# ZLS-028.net
KiCad netlist of a schematic drawn in Altium Designer
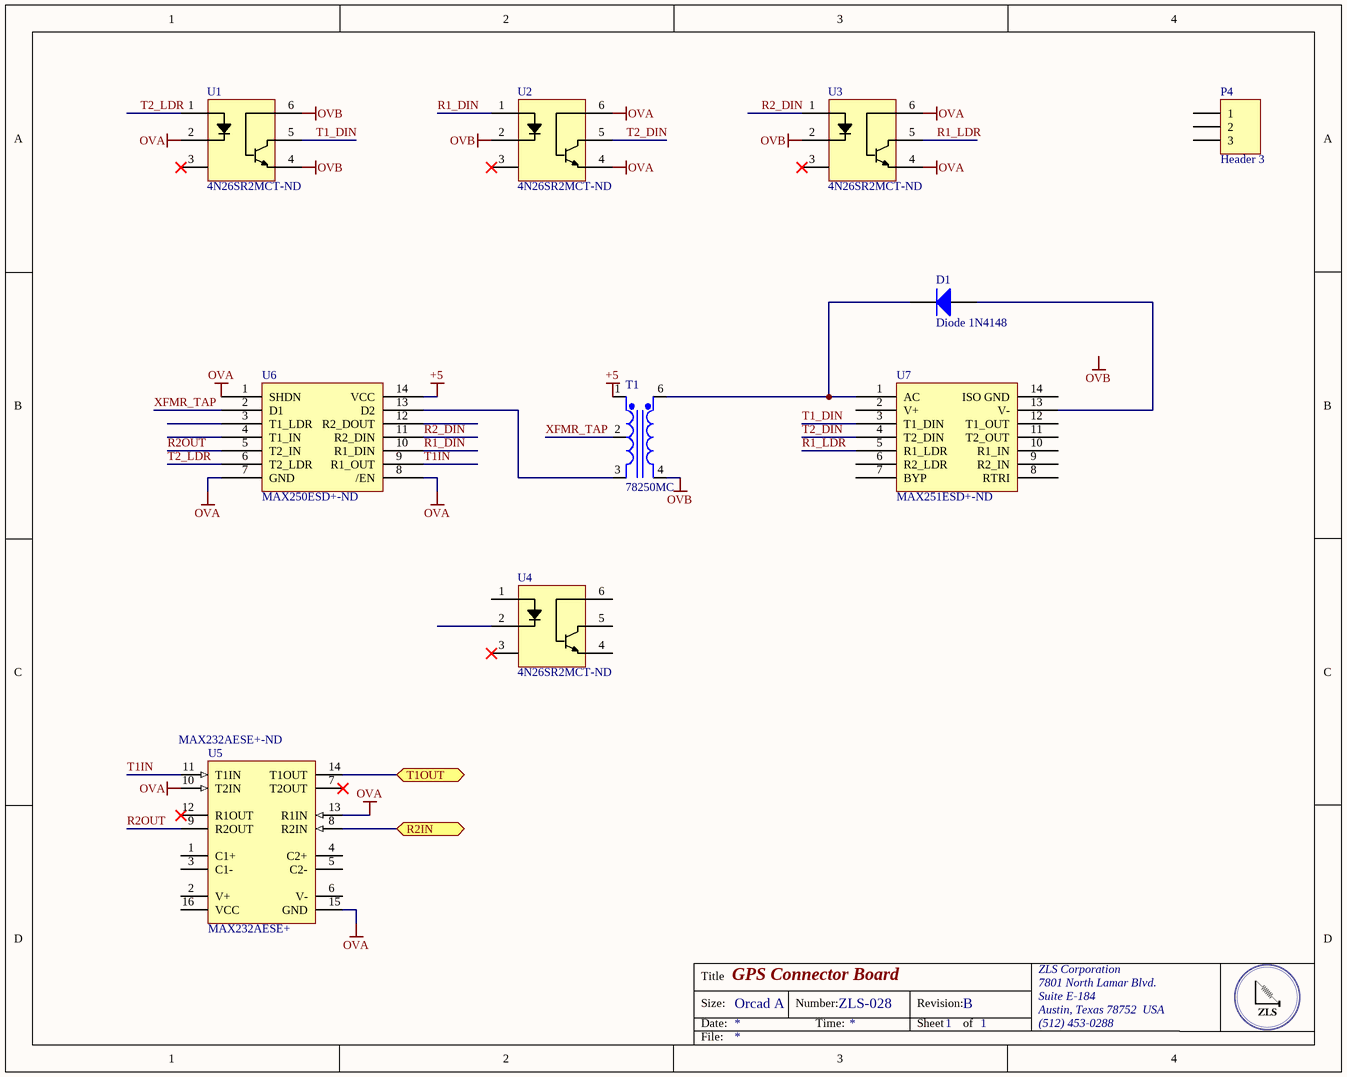
[diagram p0: ZLS-028.SchDoc]

(export (version "E")
  (design (tool "Eeschema 10.0.6"))
  (components
    (comp (ref "D1")
      (value "Diode 1N4148")
      (footprint "DO-35")
      (description "High Conductance Fast Diode")
      (fields (field (name "PUBLISHER") "Altium Limited"))
      (libsource (lib "Miscellaneous Devices") (part "Diode 1N4148"))
    )
    (comp (ref "P4")
      (value "Header 3")
      (footprint "HDR1X3")
      (description "Header, 3-Pin")
      (fields (field (name "PUBLISHER") "Altium Limited"))
      (libsource (lib "Miscellaneous Connectors") (part "Header 3"))
    )
    (comp (ref "T1")
      (value "78250MC")
      (footprint "78250MC")
      (description "Center-Tapped Transformer")
      (fields (field (name "MANUFACTURER") "Murata Power Solutions Inc."))
      (libsource (lib "Miscellaneous Devices") (part "Trans CT"))
    )
    (comp (ref "U1")
      (value "4N26")
      (footprint "6-SMD Gull Wing")
      (description "OPTOISO 4.17KV TRANS W/BASE 6SMD")
      (fields
        (field (name "SUPPLIER PART NUMBER 1") "4N26SR2MCT-ND")
        (field (name "MANUFACTURER") "ON Semiconductor")
        (field (name "MANUFACTURER PART NUMBER") "4N26SR2M")
      )
      (libsource (lib "ZLS_Schematic_lib") (part "4N26"))
    )
    (comp (ref "U2")
      (value "4N26")
      (footprint "6-SMD Gull Wing")
      (description "OPTOISO 4.17KV TRANS W/BASE 6SMD")
      (fields
        (field (name "SUPPLIER PART NUMBER 1") "4N26SR2MCT-ND")
        (field (name "MANUFACTURER") "ON Semiconductor")
        (field (name "MANUFACTURER PART NUMBER") "4N26SR2M")
      )
      (libsource (lib "ZLS_Schematic_lib") (part "4N26"))
    )
    (comp (ref "U3")
      (value "4N26")
      (footprint "6-SMD Gull Wing")
      (description "OPTOISO 4.17KV TRANS W/BASE 6SMD")
      (fields
        (field (name "SUPPLIER PART NUMBER 1") "4N26SR2MCT-ND")
        (field (name "MANUFACTURER") "ON Semiconductor")
        (field (name "MANUFACTURER PART NUMBER") "4N26SR2M")
      )
      (libsource (lib "ZLS_Schematic_lib") (part "4N26"))
    )
    (comp (ref "U4")
      (value "4N26")
      (footprint "6-SMD Gull Wing")
      (description "OPTOISO 4.17KV TRANS W/BASE 6SMD")
      (fields
        (field (name "SUPPLIER PART NUMBER 1") "4N26SR2MCT-ND")
        (field (name "MANUFACTURER") "ON Semiconductor")
        (field (name "MANUFACTURER PART NUMBER") "4N26SR2M")
      )
      (libsource (lib "ZLS_Schematic_lib") (part "4N26"))
    )
    (comp (ref "U5")
      (value "MAX232AESE+")
      (footprint "MAXM-S16+5_L")
      (description "IC TXRX 2/2 FULL RS232 16SOIC")
      (fields
        (field (name "SUPPLIER PART NUMBER 1") "MAX232AESE+-ND")
        (field (name "MANUFACTURER") "Maxim Integrated")
      )
      (libsource (lib "Altium Content Vault") (part "CMP-1675-00002-1"))
    )
    (comp (ref "U6")
      (value "MAX250ESD+")
      (footprint "MAX250ESD+")
      (fields (field (name "SUPPLIER PART NUMBER 1") "MAX250ESD+-ND"))
      (libsource (lib "ZLS_Schematic_lib") (part "MAX250ESD+"))
    )
    (comp (ref "U7")
      (value "MAX251ESD+")
      (footprint "MAX250ESD+")
      (fields
        (field (name "SUPPLIER PART NUMBER 1") "MAX251ESD+-ND")
        (field (name "MANUFACTURER") "Maxim Integrated")
      )
      (libsource (lib "ZLS_Schematic_lib") (part "MAX251ESD+"))
    )
  )
  (nets
    (net (code "1") (name "+5") (class "Default")
      (node (ref "T1") (pin "1") (pinfunction "Sec+_1") (pintype "passive"))
      (node (ref "U6") (pin "14") (pinfunction "VCC_14") (pintype "passive"))
    )
    (net (code "2") (name "/R1_DIN") (class "Default")
      (node (ref "U2") (pin "1") (pinfunction "1_1") (pintype "passive"))
      (node (ref "U6") (pin "10") (pinfunction "R1_DIN_10") (pintype "passive"))
    )
    (net (code "3") (name "/R1_LDR") (class "Default")
      (node (ref "U3") (pin "5") (pinfunction "5_5") (pintype "passive"))
      (node (ref "U7") (pin "5") (pinfunction "R1_LDR_5") (pintype "passive"))
    )
    (net (code "4") (name "/R2IN") (class "Default")
      (node (ref "U5") (pin "8") (pinfunction "R2IN_8") (pintype "input"))
    )
    (net (code "5") (name "/R2OUT") (class "Default")
      (node (ref "U5") (pin "9") (pinfunction "R2OUT_9") (pintype "tri_state"))
      (node (ref "U6") (pin "5") (pinfunction "T2_IN_5") (pintype "passive"))
    )
    (net (code "6") (name "/R2_DIN") (class "Default")
      (node (ref "U3") (pin "1") (pinfunction "1_1") (pintype "passive"))
      (node (ref "U6") (pin "11") (pinfunction "R2_DIN_11") (pintype "passive"))
    )
    (net (code "7") (name "/T1IN") (class "Default")
      (node (ref "U5") (pin "11") (pinfunction "T1IN_11") (pintype "input"))
      (node (ref "U6") (pin "9") (pinfunction "R1_OUT_9") (pintype "passive"))
    )
    (net (code "8") (name "/T1OUT") (class "Default")
      (node (ref "U5") (pin "14") (pinfunction "T1OUT_14") (pintype "tri_state"))
    )
    (net (code "9") (name "/T1_DIN") (class "Default")
      (node (ref "U1") (pin "5") (pinfunction "5_5") (pintype "passive"))
      (node (ref "U7") (pin "3") (pinfunction "T1_DIN_3") (pintype "passive"))
    )
    (net (code "10") (name "/T2_DIN") (class "Default")
      (node (ref "U2") (pin "5") (pinfunction "5_5") (pintype "passive"))
      (node (ref "U7") (pin "4") (pinfunction "T2_DIN_4") (pintype "passive"))
    )
    (net (code "11") (name "/T2_LDR") (class "Default")
      (node (ref "U1") (pin "1") (pinfunction "1_1") (pintype "passive"))
      (node (ref "U6") (pin "6") (pinfunction "T2_LDR_6") (pintype "passive"))
    )
    (net (code "12") (name "/XFMR_TAP") (class "Default")
      (node (ref "T1") (pin "2") (pinfunction "PriCT_2") (pintype "passive"))
      (node (ref "U6") (pin "2") (pinfunction "D1_2") (pintype "passive"))
    )
    (net (code "13") (name "Net-(D1-A)") (class "Default")
      (node (ref "D1") (pin "1") (pinfunction "A_1") (pintype "passive"))
      (node (ref "U7") (pin "13") (pinfunction "V-_13") (pintype "passive"))
    )
    (net (code "14") (name "Net-(D1-K)") (class "Default")
      (node (ref "D1") (pin "2") (pinfunction "K_2") (pintype "passive"))
      (node (ref "T1") (pin "6") (pinfunction "Pri+_6") (pintype "passive"))
      (node (ref "U7") (pin "1") (pinfunction "AC_1") (pintype "passive"))
    )
    (net (code "15") (name "Net-(T1-Sec-)") (class "Default")
      (node (ref "T1") (pin "3") (pinfunction "Sec-_3") (pintype "passive"))
      (node (ref "U6") (pin "13") (pinfunction "D2_13") (pintype "passive"))
    )
    (net (code "16") (name "OVA") (class "Default")
      (node (ref "U1") (pin "2") (pinfunction "2_2") (pintype "passive"))
      (node (ref "U2") (pin "4") (pinfunction "4_4") (pintype "passive"))
      (node (ref "U2") (pin "6") (pinfunction "6_6") (pintype "passive"))
      (node (ref "U3") (pin "4") (pinfunction "4_4") (pintype "passive"))
      (node (ref "U3") (pin "6") (pinfunction "6_6") (pintype "passive"))
      (node (ref "U5") (pin "10") (pinfunction "T2IN_10") (pintype "input"))
      (node (ref "U5") (pin "13") (pinfunction "R1IN_13") (pintype "input"))
      (node (ref "U5") (pin "15") (pinfunction "GND_15") (pintype "power_in"))
      (node (ref "U6") (pin "1") (pinfunction "SHDN_1") (pintype "passive"))
      (node (ref "U6") (pin "7") (pinfunction "GND_7") (pintype "passive"))
      (node (ref "U6") (pin "8") (pinfunction "/EN_8") (pintype "passive"))
    )
    (net (code "17") (name "OVB") (class "Default")
      (node (ref "T1") (pin "4") (pinfunction "Pri-_4") (pintype "passive"))
      (node (ref "U1") (pin "4") (pinfunction "4_4") (pintype "passive"))
      (node (ref "U1") (pin "6") (pinfunction "6_6") (pintype "passive"))
      (node (ref "U2") (pin "2") (pinfunction "2_2") (pintype "passive"))
      (node (ref "U3") (pin "2") (pinfunction "2_2") (pintype "passive"))
    )
    (net (code "18") (name "unconnected-(P4-Pad1)") (class "Default")
      (node (ref "P4") (pin "1") (pinfunction "1_1") (pintype "passive"))
    )
    (net (code "19") (name "unconnected-(P4-Pad2)") (class "Default")
      (node (ref "P4") (pin "2") (pinfunction "2_2") (pintype "passive"))
    )
    (net (code "20") (name "unconnected-(P4-Pad3)") (class "Default")
      (node (ref "P4") (pin "3") (pinfunction "3_3") (pintype "passive"))
    )
    (net (code "21") (name "unconnected-(U1-Pad3)") (class "Default")
      (node (ref "U1") (pin "3") (pinfunction "3_3") (pintype "passive+no_connect"))
    )
    (net (code "22") (name "unconnected-(U2-Pad3)") (class "Default")
      (node (ref "U2") (pin "3") (pinfunction "3_3") (pintype "passive+no_connect"))
    )
    (net (code "23") (name "unconnected-(U3-Pad3)") (class "Default")
      (node (ref "U3") (pin "3") (pinfunction "3_3") (pintype "passive+no_connect"))
    )
    (net (code "24") (name "unconnected-(U4-Pad1)") (class "Default")
      (node (ref "U4") (pin "1") (pinfunction "1_1") (pintype "passive"))
    )
    (net (code "25") (name "unconnected-(U4-Pad2)") (class "Default")
      (node (ref "U4") (pin "2") (pinfunction "2_2") (pintype "passive"))
    )
    (net (code "26") (name "unconnected-(U4-Pad3)") (class "Default")
      (node (ref "U4") (pin "3") (pinfunction "3_3") (pintype "passive+no_connect"))
    )
    (net (code "27") (name "unconnected-(U4-Pad4)") (class "Default")
      (node (ref "U4") (pin "4") (pinfunction "4_4") (pintype "passive"))
    )
    (net (code "28") (name "unconnected-(U4-Pad5)") (class "Default")
      (node (ref "U4") (pin "5") (pinfunction "5_5") (pintype "passive"))
    )
    (net (code "29") (name "unconnected-(U4-Pad6)") (class "Default")
      (node (ref "U4") (pin "6") (pinfunction "6_6") (pintype "passive"))
    )
    (net (code "30") (name "unconnected-(U5-C1+-Pad1)") (class "Default")
      (node (ref "U5") (pin "1") (pinfunction "C1+_1") (pintype "passive"))
    )
    (net (code "31") (name "unconnected-(U5-C1--Pad3)") (class "Default")
      (node (ref "U5") (pin "3") (pinfunction "C1-_3") (pintype "passive"))
    )
    (net (code "32") (name "unconnected-(U5-C2+-Pad4)") (class "Default")
      (node (ref "U5") (pin "4") (pinfunction "C2+_4") (pintype "passive"))
    )
    (net (code "33") (name "unconnected-(U5-C2--Pad5)") (class "Default")
      (node (ref "U5") (pin "5") (pinfunction "C2-_5") (pintype "passive"))
    )
    (net (code "34") (name "unconnected-(U5-R1OUT-Pad12)") (class "Default")
      (node (ref "U5") (pin "12") (pinfunction "R1OUT_12") (pintype "tri_state+no_connect"))
    )
    (net (code "35") (name "unconnected-(U5-T2OUT-Pad7)") (class "Default")
      (node (ref "U5") (pin "7") (pinfunction "T2OUT_7") (pintype "tri_state+no_connect"))
    )
    (net (code "36") (name "unconnected-(U5-V+-Pad2)") (class "Default")
      (node (ref "U5") (pin "2") (pinfunction "V+_2") (pintype "power_in"))
    )
    (net (code "37") (name "unconnected-(U5-V--Pad6)") (class "Default")
      (node (ref "U5") (pin "6") (pinfunction "V-_6") (pintype "power_in"))
    )
    (net (code "38") (name "unconnected-(U5-VCC-Pad16)") (class "Default")
      (node (ref "U5") (pin "16") (pinfunction "VCC_16") (pintype "power_in"))
    )
    (net (code "39") (name "unconnected-(U6-R2_DOUT-Pad12)") (class "Default")
      (node (ref "U6") (pin "12") (pinfunction "R2_DOUT_12") (pintype "passive"))
    )
    (net (code "40") (name "unconnected-(U6-T1_IN-Pad4)") (class "Default")
      (node (ref "U6") (pin "4") (pinfunction "T1_IN_4") (pintype "passive"))
    )
    (net (code "41") (name "unconnected-(U6-T1_LDR-Pad3)") (class "Default")
      (node (ref "U6") (pin "3") (pinfunction "T1_LDR_3") (pintype "passive"))
    )
    (net (code "42") (name "unconnected-(U7-BYP-Pad7)") (class "Default")
      (node (ref "U7") (pin "7") (pinfunction "BYP_7") (pintype "passive"))
    )
    (net (code "43") (name "unconnected-(U7-ISO_GND-Pad14)") (class "Default")
      (node (ref "U7") (pin "14") (pinfunction "ISO_GND_14") (pintype "passive"))
    )
    (net (code "44") (name "unconnected-(U7-R1_IN-Pad10)") (class "Default")
      (node (ref "U7") (pin "10") (pinfunction "R1_IN_10") (pintype "passive"))
    )
    (net (code "45") (name "unconnected-(U7-R2_IN-Pad9)") (class "Default")
      (node (ref "U7") (pin "9") (pinfunction "R2_IN_9") (pintype "passive"))
    )
    (net (code "46") (name "unconnected-(U7-R2_LDR-Pad6)") (class "Default")
      (node (ref "U7") (pin "6") (pinfunction "R2_LDR_6") (pintype "passive"))
    )
    (net (code "47") (name "unconnected-(U7-RTRI-Pad8)") (class "Default")
      (node (ref "U7") (pin "8") (pinfunction "RTRI_8") (pintype "passive"))
    )
    (net (code "48") (name "unconnected-(U7-T1_OUT-Pad12)") (class "Default")
      (node (ref "U7") (pin "12") (pinfunction "T1_OUT_12") (pintype "passive"))
    )
    (net (code "49") (name "unconnected-(U7-T2_OUT-Pad11)") (class "Default")
      (node (ref "U7") (pin "11") (pinfunction "T2_OUT_11") (pintype "passive"))
    )
    (net (code "50") (name "unconnected-(U7-V+-Pad2)") (class "Default")
      (node (ref "U7") (pin "2") (pinfunction "V+_2") (pintype "passive"))
    )
  )
)
